# XBEE3_Thing_Plus.net
KiCad netlist of a schematic drawn in EAGLE
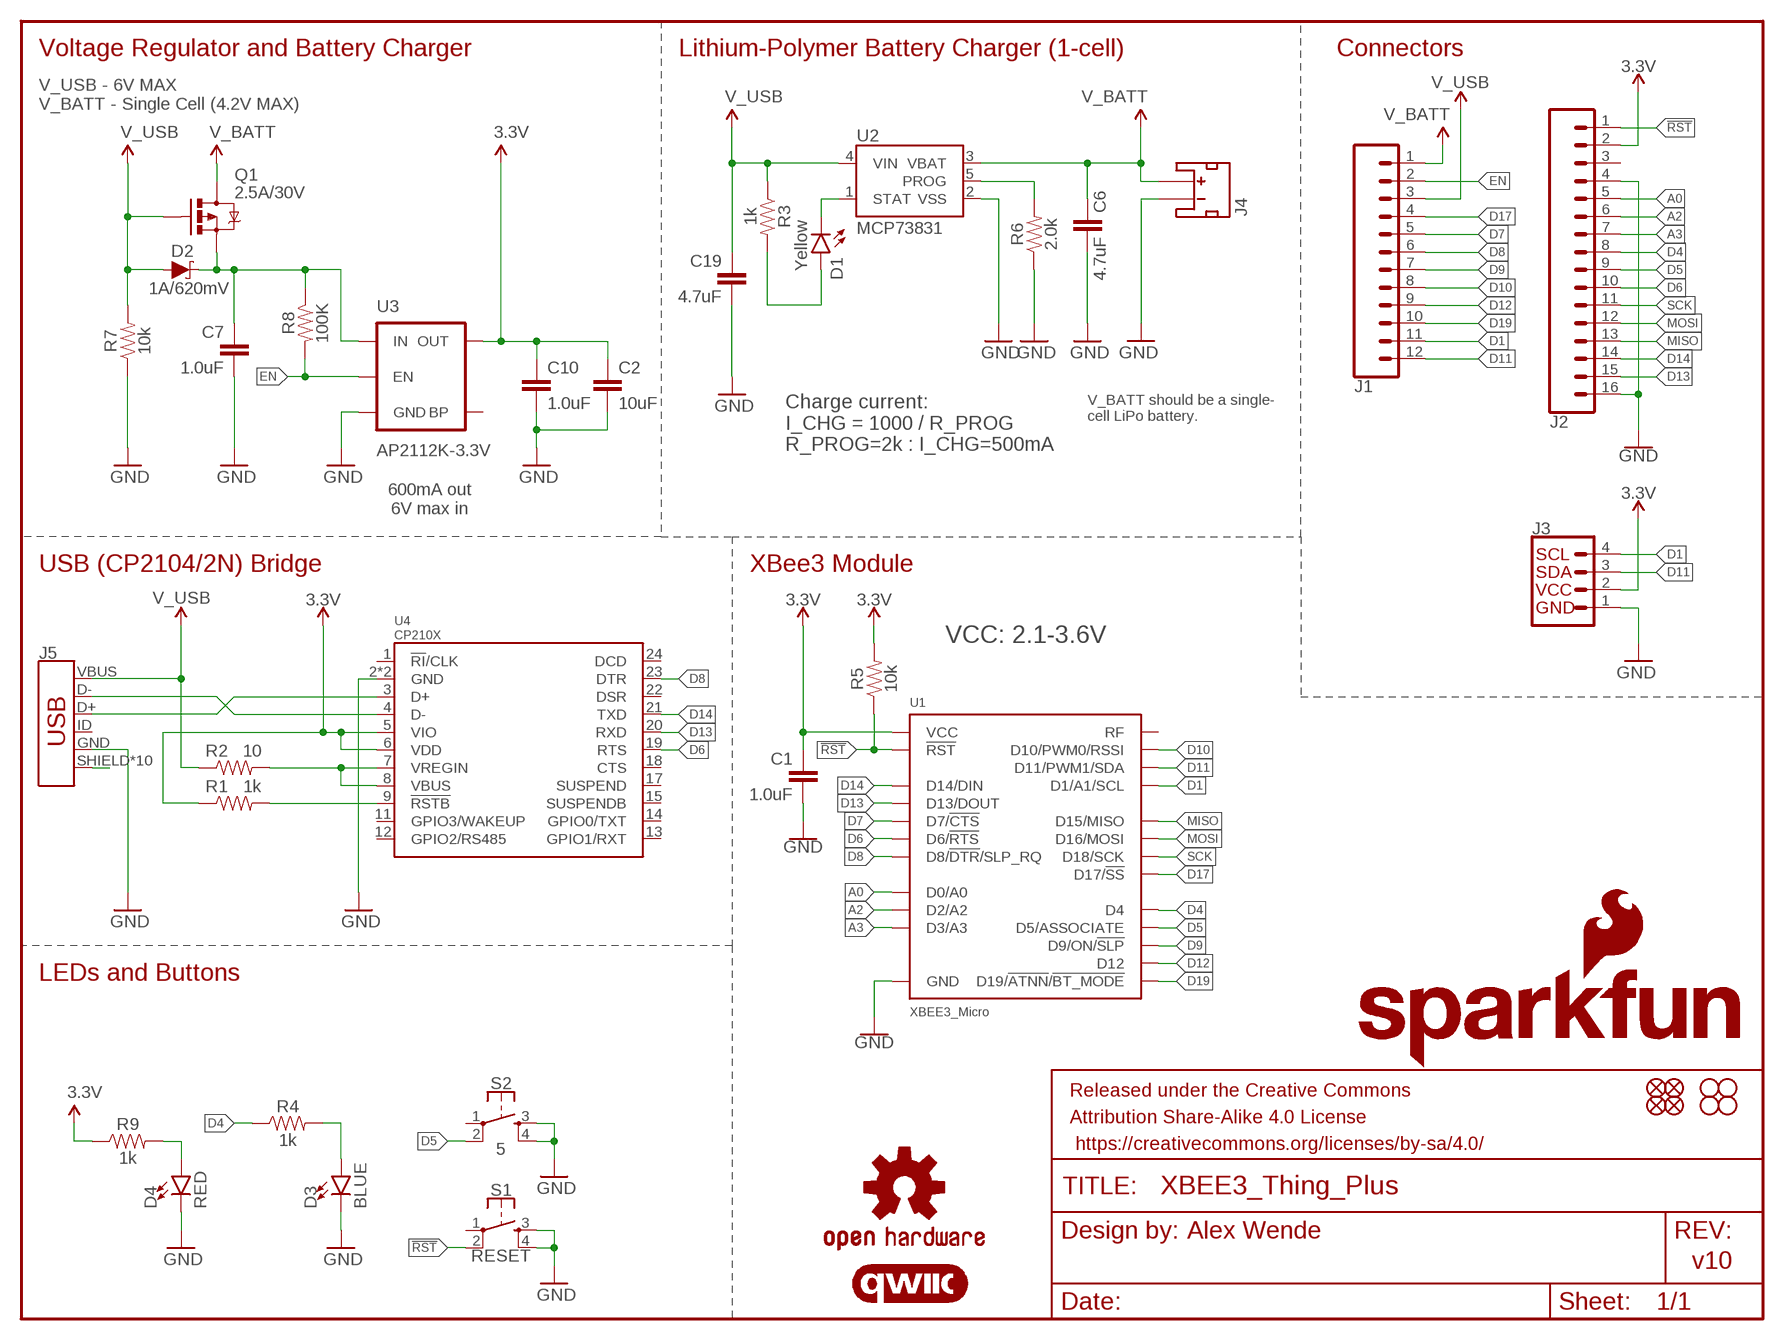
[diagram p0: schematic, sheet 1]

(export (version "E")
  (design (tool "Eeschema 10.0.6"))
  (components
    (comp (ref "C1")
      (value "1.0uF")
      (footprint "eagle-import:0603")
      (libsource (lib "eagle-import") (part "1.0UF-0603-16V-10%"))
    )
    (comp (ref "C2")
      (value "10uF")
      (footprint "eagle-import:0603")
      (libsource (lib "eagle-import") (part "10UF-0603-6.3V-20%"))
    )
    (comp (ref "C6")
      (value "4.7uF")
      (footprint "eagle-import:0603")
      (libsource (lib "eagle-import") (part "4.7UF-0603-6.3V-(10%)"))
    )
    (comp (ref "C7")
      (value "1.0uF")
      (footprint "eagle-import:0603")
      (libsource (lib "eagle-import") (part "1.0UF-0603-16V-10%-X7R"))
    )
    (comp (ref "C10")
      (value "1.0uF")
      (footprint "eagle-import:0402")
      (libsource (lib "eagle-import") (part "1.0UF-0402-16V-10%"))
    )
    (comp (ref "C19")
      (value "4.7uF")
      (footprint "eagle-import:0603")
      (libsource (lib "eagle-import") (part "4.7UF-0603-6.3V-(10%)"))
    )
    (comp (ref "D1")
      (value "Yellow")
      (footprint "eagle-import:LED-0603")
      (libsource (lib "eagle-import") (part "LED-YELLOW0603"))
    )
    (comp (ref "D2")
      (value "1A/620mV")
      (footprint "eagle-import:SOD-323")
      (libsource (lib "eagle-import") (part "DIODE-SCHOTTKY-BAT20J"))
    )
    (comp (ref "D3")
      (value "BLUE")
      (footprint "eagle-import:LED-0603")
      (libsource (lib "eagle-import") (part "LED-BLUE0603"))
    )
    (comp (ref "D4")
      (value "RED")
      (footprint "eagle-import:LED-0603")
      (libsource (lib "eagle-import") (part "LED-RED0603"))
    )
    (comp (ref "FD1")
      (value "FIDUCIALUFIDUCIAL")
      (footprint "eagle-import:FIDUCIAL-MICRO")
      (libsource (lib "eagle-import") (part "FIDUCIALUFIDUCIAL"))
    )
    (comp (ref "FD2")
      (value "FIDUCIALUFIDUCIAL")
      (footprint "eagle-import:FIDUCIAL-MICRO")
      (libsource (lib "eagle-import") (part "FIDUCIALUFIDUCIAL"))
    )
    (comp (ref "FD3")
      (value "FIDUCIALUFIDUCIAL")
      (footprint "eagle-import:FIDUCIAL-MICRO")
      (libsource (lib "eagle-import") (part "FIDUCIALUFIDUCIAL"))
    )
    (comp (ref "FD4")
      (value "FIDUCIALUFIDUCIAL")
      (footprint "eagle-import:FIDUCIAL-MICRO")
      (libsource (lib "eagle-import") (part "FIDUCIALUFIDUCIAL"))
    )
    (comp (ref "FRAME1")
      (value "FRAME-LETTER")
      (footprint "eagle-import:CREATIVE_COMMONS")
      (libsource (lib "eagle-import") (part "FRAME-LETTER"))
    )
    (comp (ref "H1")
      (value "STAND-OFF")
      (footprint "eagle-import:STAND-OFF")
      (libsource (lib "eagle-import") (part "STAND-OFF"))
    )
    (comp (ref "H2")
      (value "STAND-OFF")
      (footprint "eagle-import:STAND-OFF")
      (libsource (lib "eagle-import") (part "STAND-OFF"))
    )
    (comp (ref "H3")
      (value "STAND-OFF")
      (footprint "eagle-import:STAND-OFF")
      (libsource (lib "eagle-import") (part "STAND-OFF"))
    )
    (comp (ref "H4")
      (value "STAND-OFF")
      (footprint "eagle-import:STAND-OFF")
      (libsource (lib "eagle-import") (part "STAND-OFF"))
    )
    (comp (ref "J1")
      (value "CONN_12SM_SQ_NO_SILK")
      (footprint "eagle-import:1X12_SM_SQ_NOSILK")
      (libsource (lib "eagle-import") (part "CONN_12SM_SQ_NO_SILK"))
    )
    (comp (ref "J2")
      (value "CONN_161X16_SM_SQ_NOSILK")
      (footprint "eagle-import:1X16_SM_SQ_NOSILK")
      (libsource (lib "eagle-import") (part "CONN_161X16_SM_SQ_NOSILK"))
    )
    (comp (ref "J3")
      (value "QWIIC_CONNECTORJS-1MM")
      (footprint "eagle-import:JST04_1MM_RA")
      (libsource (lib "eagle-import") (part "QWIIC_CONNECTORJS-1MM"))
    )
    (comp (ref "J4")
      (value "JST_2MM_MALE")
      (footprint "eagle-import:JST-2-SMD")
      (libsource (lib "eagle-import") (part "JST_2MM_MALE"))
    )
    (comp (ref "J5")
      (value "USB_MICRO-B_HALF_PTH_MILL")
      (footprint "eagle-import:USB-MICROB-PTH-MILL")
      (libsource (lib "eagle-import") (part "USB_MICRO-B_HALF_PTH_MILL"))
    )
    (comp (ref "LOGO1")
      (value "SFE_LOGO_NAME_FLAME.1_INCH")
      (footprint "eagle-import:SFE_LOGO_NAME_FLAME_.1")
      (libsource (lib "eagle-import") (part "SFE_LOGO_NAME_FLAME.1_INCH"))
    )
    (comp (ref "LOGO2")
      (value "OSHW-LOGOS")
      (footprint "eagle-import:OSHW-LOGO-S")
      (libsource (lib "eagle-import") (part "OSHW-LOGOS"))
    )
    (comp (ref "Q1")
      (value "2.5A/30V")
      (footprint "eagle-import:SOT23-3@1")
      (libsource (lib "eagle-import") (part "MOSFET-PCHANNELDMG2307L"))
    )
    (comp (ref "R1")
      (value "1k")
      (footprint "eagle-import:0603")
      (libsource (lib "eagle-import") (part "1KOHM-0603-1/10W-1%"))
    )
    (comp (ref "R2")
      (value "10")
      (footprint "eagle-import:0603")
      (libsource (lib "eagle-import") (part "10OHM-0603-1/10W-1%"))
    )
    (comp (ref "R3")
      (value "1k")
      (footprint "eagle-import:0603")
      (libsource (lib "eagle-import") (part "1KOHM-0603-1/10W-1%"))
    )
    (comp (ref "R4")
      (value "1k")
      (footprint "eagle-import:0603")
      (libsource (lib "eagle-import") (part "1KOHM-0603-1/10W-1%"))
    )
    (comp (ref "R5")
      (value "10k")
      (footprint "eagle-import:0603")
      (libsource (lib "eagle-import") (part "10KOHM-0603-1/10W-1%"))
    )
    (comp (ref "R6")
      (value "2.0k")
      (footprint "eagle-import:0603")
      (libsource (lib "eagle-import") (part "2.0KOHM1/10W5%(0603)"))
    )
    (comp (ref "R7")
      (value "10k")
      (footprint "eagle-import:0603")
      (libsource (lib "eagle-import") (part "10KOHM-0603-1/10W-1%"))
    )
    (comp (ref "R8")
      (value "100K")
      (footprint "eagle-import:0402")
      (libsource (lib "eagle-import") (part "100KOHM-0402-1/16W-1%"))
    )
    (comp (ref "R9")
      (value "1k")
      (footprint "eagle-import:0603")
      (libsource (lib "eagle-import") (part "1KOHM-0603-1/10W-1%"))
    )
    (comp (ref "S1")
      (value "RESET")
      (footprint "eagle-import:TACTILE_SWITCH_SMD_4.6X2.8MM")
      (libsource (lib "eagle-import") (part "MOMENTARY-SWITCH-SPST-2-SMD-4.6X2.8MM"))
    )
    (comp (ref "S2")
      (value "5")
      (footprint "eagle-import:TACTILE_SWITCH_SMD_4.6X2.8MM")
      (libsource (lib "eagle-import") (part "MOMENTARY-SWITCH-SPST-2-SMD-4.6X2.8MM"))
    )
    (comp (ref "U$63")
      (value "QWIIC_LOGO_5MM")
      (footprint "eagle-import:QWIIC_5MM")
      (libsource (lib "eagle-import") (part "QWIIC_LOGO_5MM"))
    )
    (comp (ref "U1")
      (value "XBEE3_Micro")
      (footprint "eagle-import:XBEE3")
      (libsource (lib "eagle-import") (part "XBEE3"))
    )
    (comp (ref "U2")
      (value "MCP73831")
      (footprint "eagle-import:SOT23-5")
      (libsource (lib "eagle-import") (part "MCP73831"))
    )
    (comp (ref "U3")
      (value "AP2112K-3.3V")
      (footprint "eagle-import:SOT23-5")
      (libsource (lib "eagle-import") (part "V_REG_LDOSMD"))
    )
    (comp (ref "U4")
      (value "CP210X")
      (footprint "eagle-import:QFN24")
      (libsource (lib "eagle-import") (part "CP2102N"))
    )
  )
  (nets
    (net (code "1") (name "/~{RST}") (class "Default")
      (node (ref "J2") (pin "1") (pinfunction "1_1") (pintype "passive"))
      (node (ref "R5") (pin "1") (pinfunction "1_1") (pintype "passive"))
      (node (ref "S1") (pin "2") (pinfunction "2_2") (pintype "passive"))
      (node (ref "U1") (pin "P$6") (pinfunction "~{RST}_P$6") (pintype "input"))
    )
    (net (code "2") (name "3.3V") (class "Default")
      (node (ref "C1") (pin "1") (pinfunction "1_1") (pintype "passive"))
      (node (ref "C10") (pin "1") (pinfunction "1_1") (pintype "passive"))
      (node (ref "C2") (pin "1") (pinfunction "1_1") (pintype "passive"))
      (node (ref "J2") (pin "2") (pinfunction "2_2") (pintype "passive"))
      (node (ref "J3") (pin "2") (pinfunction "2_2") (pintype "power_in"))
      (node (ref "R1") (pin "1") (pinfunction "1_1") (pintype "passive"))
      (node (ref "R5") (pin "2") (pinfunction "2_2") (pintype "passive"))
      (node (ref "R9") (pin "1") (pinfunction "1_1") (pintype "passive"))
      (node (ref "U1") (pin "P$2") (pinfunction "VCC_P$2") (pintype "bidirectional"))
      (node (ref "U3") (pin "5") (pinfunction "OUT_5") (pintype "passive"))
      (node (ref "U4") (pin "5") (pinfunction "VIO_5") (pintype "bidirectional"))
      (node (ref "U4") (pin "6") (pinfunction "VDD_6") (pintype "bidirectional"))
    )
    (net (code "3") (name "A0") (class "Default")
      (node (ref "J2") (pin "5") (pinfunction "5_5") (pintype "passive"))
      (node (ref "U1") (pin "P$31") (pinfunction "D0/A0_P$31") (pintype "bidirectional"))
    )
    (net (code "4") (name "A2") (class "Default")
      (node (ref "J2") (pin "6") (pinfunction "6_6") (pintype "passive"))
      (node (ref "U1") (pin "P$29") (pinfunction "D2/A2_P$29") (pintype "bidirectional"))
    )
    (net (code "5") (name "A3") (class "Default")
      (node (ref "J2") (pin "7") (pinfunction "7_7") (pintype "passive"))
      (node (ref "U1") (pin "P$28") (pinfunction "D3/A3_P$28") (pintype "bidirectional"))
    )
    (net (code "6") (name "D1") (class "Default")
      (node (ref "J1") (pin "11") (pinfunction "11_11") (pintype "passive"))
      (node (ref "J3") (pin "4") (pinfunction "4_4") (pintype "passive"))
      (node (ref "U1") (pin "P$30") (pinfunction "D1/A1/SCL_P$30") (pintype "bidirectional"))
    )
    (net (code "7") (name "D4") (class "Default")
      (node (ref "J2") (pin "8") (pinfunction "8_8") (pintype "passive"))
      (node (ref "R4") (pin "1") (pinfunction "1_1") (pintype "passive"))
      (node (ref "U1") (pin "P$23") (pinfunction "D4_P$23") (pintype "bidirectional"))
    )
    (net (code "8") (name "D5") (class "Default")
      (node (ref "J2") (pin "9") (pinfunction "9_9") (pintype "passive"))
      (node (ref "S2") (pin "2") (pinfunction "2_2") (pintype "passive"))
      (node (ref "U1") (pin "P$26") (pinfunction "D5/ASSOCIATE_P$26") (pintype "bidirectional"))
    )
    (net (code "9") (name "D6") (class "Default")
      (node (ref "J2") (pin "10") (pinfunction "10_10") (pintype "passive"))
      (node (ref "U1") (pin "P$27") (pinfunction "D6/~{RTS}_P$27") (pintype "bidirectional"))
      (node (ref "U4") (pin "19") (pinfunction "RTS_19") (pintype "bidirectional"))
    )
    (net (code "10") (name "D7") (class "Default")
      (node (ref "J1") (pin "5") (pinfunction "5_5") (pintype "passive"))
      (node (ref "U1") (pin "P$24") (pinfunction "D7/~{CTS}_P$24") (pintype "bidirectional"))
    )
    (net (code "11") (name "D8") (class "Default")
      (node (ref "J1") (pin "6") (pinfunction "6_6") (pintype "passive"))
      (node (ref "U1") (pin "P$9") (pinfunction "D8/~{DTR}/SLP_RQ_P$9") (pintype "bidirectional"))
      (node (ref "U4") (pin "23") (pinfunction "DTR_23") (pintype "bidirectional"))
    )
    (net (code "12") (name "D9") (class "Default")
      (node (ref "J1") (pin "7") (pinfunction "7_7") (pintype "passive"))
      (node (ref "U1") (pin "P$25") (pinfunction "D9/ON/~{SLP}_P$25") (pintype "bidirectional"))
    )
    (net (code "13") (name "D10") (class "Default")
      (node (ref "J1") (pin "8") (pinfunction "8_8") (pintype "passive"))
      (node (ref "U1") (pin "P$7") (pinfunction "D10/PWM0/RSSI_P$7") (pintype "bidirectional"))
    )
    (net (code "14") (name "D11") (class "Default")
      (node (ref "J1") (pin "12") (pinfunction "12_12") (pintype "passive"))
      (node (ref "J3") (pin "3") (pinfunction "3_3") (pintype "passive"))
      (node (ref "U1") (pin "P$8") (pinfunction "D11/PWM1/SDA_P$8") (pintype "bidirectional"))
    )
    (net (code "15") (name "D12") (class "Default")
      (node (ref "J1") (pin "9") (pinfunction "9_9") (pintype "passive"))
      (node (ref "U1") (pin "P$5") (pinfunction "D12_P$5") (pintype "bidirectional"))
    )
    (net (code "16") (name "D13") (class "Default")
      (node (ref "J2") (pin "15") (pinfunction "15_15") (pintype "passive"))
      (node (ref "U1") (pin "P$3") (pinfunction "D13/DOUT_P$3") (pintype "bidirectional"))
      (node (ref "U4") (pin "20") (pinfunction "RXD_20") (pintype "bidirectional"))
    )
    (net (code "17") (name "D14") (class "Default")
      (node (ref "J2") (pin "14") (pinfunction "14_14") (pintype "passive"))
      (node (ref "U1") (pin "P$4") (pinfunction "D14/DIN_P$4") (pintype "bidirectional"))
      (node (ref "U4") (pin "21") (pinfunction "TXD_21") (pintype "bidirectional"))
    )
    (net (code "18") (name "D17") (class "Default")
      (node (ref "J1") (pin "4") (pinfunction "4_4") (pintype "passive"))
      (node (ref "U1") (pin "P$14") (pinfunction "D17/~{SS}_P$14") (pintype "bidirectional"))
    )
    (net (code "19") (name "D19") (class "Default")
      (node (ref "J1") (pin "10") (pinfunction "10_10") (pintype "passive"))
      (node (ref "U1") (pin "P$11") (pinfunction "D19/~{ATNN}/~{BT_MODE}_P$11") (pintype "bidirectional"))
    )
    (net (code "20") (name "EN") (class "Default")
      (node (ref "J1") (pin "2") (pinfunction "2_2") (pintype "passive"))
      (node (ref "R8") (pin "2") (pinfunction "2_2") (pintype "passive"))
      (node (ref "U3") (pin "3") (pinfunction "EN_3") (pintype "input"))
    )
    (net (code "21") (name "GND") (class "Default")
      (node (ref "C1") (pin "2") (pinfunction "2_2") (pintype "passive"))
      (node (ref "C10") (pin "2") (pinfunction "2_2") (pintype "passive"))
      (node (ref "C19") (pin "2") (pinfunction "2_2") (pintype "passive"))
      (node (ref "C2") (pin "2") (pinfunction "2_2") (pintype "passive"))
      (node (ref "C6") (pin "2") (pinfunction "2_2") (pintype "passive"))
      (node (ref "C7") (pin "2") (pinfunction "2_2") (pintype "passive"))
      (node (ref "D3") (pin "C") (pinfunction "C_C") (pintype "passive"))
      (node (ref "D4") (pin "C") (pinfunction "C_C") (pintype "passive"))
      (node (ref "J2") (pin "16") (pinfunction "16_16") (pintype "passive"))
      (node (ref "J2") (pin "4") (pinfunction "4_4") (pintype "passive"))
      (node (ref "J3") (pin "1") (pinfunction "1_1") (pintype "power_in"))
      (node (ref "J4") (pin "1") (pinfunction "-_1") (pintype "bidirectional"))
      (node (ref "J5") (pin "GND") (pinfunction "GND_GND") (pintype "power_in"))
      (node (ref "R6") (pin "1") (pinfunction "1_1") (pintype "passive"))
      (node (ref "R7") (pin "1") (pinfunction "1_1") (pintype "passive"))
      (node (ref "S1") (pin "3") (pinfunction "3_3") (pintype "passive"))
      (node (ref "S1") (pin "4") (pinfunction "4_4") (pintype "passive"))
      (node (ref "S2") (pin "3") (pinfunction "3_3") (pintype "passive"))
      (node (ref "S2") (pin "4") (pinfunction "4_4") (pintype "passive"))
      (node (ref "U1") (pin "P$1") (pinfunction "GND_P$1") (pintype "bidirectional"))
      (node (ref "U1") (pin "P$10") (pinfunction "GND_P$10") (pintype "bidirectional"))
      (node (ref "U1") (pin "P$12") (pinfunction "GND_P$12") (pintype "bidirectional"))
      (node (ref "U1") (pin "P$21") (pinfunction "GND_P$21") (pintype "bidirectional"))
      (node (ref "U1") (pin "P$32") (pinfunction "GND_P$32") (pintype "bidirectional"))
      (node (ref "U1") (pin "P$34") (pinfunction "GND_P$34") (pintype "bidirectional"))
      (node (ref "U2") (pin "2") (pinfunction "VSS_2") (pintype "power_in"))
      (node (ref "U3") (pin "2") (pinfunction "GND_2") (pintype "input"))
      (node (ref "U4") (pin "2") (pinfunction "GND_2") (pintype "bidirectional"))
      (node (ref "U4") (pin "PAD") (pinfunction "GND_PAD") (pintype "bidirectional"))
    )
    (net (code "22") (name "MISO") (class "Default")
      (node (ref "J2") (pin "13") (pinfunction "13_13") (pintype "passive"))
      (node (ref "U1") (pin "P$16") (pinfunction "D15/MISO_P$16") (pintype "bidirectional"))
    )
    (net (code "23") (name "MOSI") (class "Default")
      (node (ref "J2") (pin "12") (pinfunction "12_12") (pintype "passive"))
      (node (ref "U1") (pin "P$15") (pinfunction "D16/MOSI_P$15") (pintype "bidirectional"))
    )
    (net (code "24") (name "Net-(D1-PadA)") (class "Default")
      (node (ref "D1") (pin "A") (pinfunction "A_A") (pintype "passive"))
      (node (ref "R3") (pin "2") (pinfunction "2_2") (pintype "passive"))
    )
    (net (code "25") (name "Net-(D3-PadA)") (class "Default")
      (node (ref "D3") (pin "A") (pinfunction "A_A") (pintype "passive"))
      (node (ref "R4") (pin "2") (pinfunction "2_2") (pintype "passive"))
    )
    (net (code "26") (name "Net-(D4-PadA)") (class "Default")
      (node (ref "D4") (pin "A") (pinfunction "A_A") (pintype "passive"))
      (node (ref "R9") (pin "2") (pinfunction "2_2") (pintype "passive"))
    )
    (net (code "27") (name "Net-(J5-PadSHIELD)") (class "Default")
      (node (ref "J5") (pin "SHIELD") (pinfunction "SHIELD_SHIELD") (pintype "bidirectional"))
      (node (ref "J5") (pin "SHIELD10") (pinfunction "SHIELD_SHIELD10") (pintype "bidirectional"))
      (node (ref "J5") (pin "SHIELD2") (pinfunction "SHIELD_SHIELD2") (pintype "bidirectional"))
      (node (ref "J5") (pin "SHIELD3") (pinfunction "SHIELD_SHIELD3") (pintype "bidirectional"))
      (node (ref "J5") (pin "SHIELD4") (pinfunction "SHIELD_SHIELD4") (pintype "bidirectional"))
      (node (ref "J5") (pin "SHIELD5") (pinfunction "SHIELD_SHIELD5") (pintype "bidirectional"))
      (node (ref "J5") (pin "SHIELD6") (pinfunction "SHIELD_SHIELD6") (pintype "bidirectional"))
      (node (ref "J5") (pin "SHIELD7") (pinfunction "SHIELD_SHIELD7") (pintype "bidirectional"))
      (node (ref "J5") (pin "SHIELD8") (pinfunction "SHIELD_SHIELD8") (pintype "bidirectional"))
      (node (ref "J5") (pin "SHIELD9") (pinfunction "SHIELD_SHIELD9") (pintype "bidirectional"))
    )
    (net (code "28") (name "Net-(Q1-S)") (class "Default")
      (node (ref "C7") (pin "1") (pinfunction "1_1") (pintype "passive"))
      (node (ref "D2") (pin "C") (pinfunction "C_C") (pintype "passive"))
      (node (ref "Q1") (pin "2") (pinfunction "S_2") (pintype "passive"))
      (node (ref "R8") (pin "1") (pinfunction "1_1") (pintype "passive"))
      (node (ref "U3") (pin "1") (pinfunction "IN_1") (pintype "input"))
    )
    (net (code "29") (name "Net-(U2-PROG)") (class "Default")
      (node (ref "R6") (pin "2") (pinfunction "2_2") (pintype "passive"))
      (node (ref "U2") (pin "5") (pinfunction "PROG_5") (pintype "input"))
    )
    (net (code "30") (name "Net-(U2-STAT)") (class "Default")
      (node (ref "D1") (pin "C") (pinfunction "C_C") (pintype "passive"))
      (node (ref "U2") (pin "1") (pinfunction "STAT_1") (pintype "output"))
    )
    (net (code "31") (name "Net-(U4-D+)") (class "Default")
      (node (ref "J5") (pin "D+") (pinfunction "D+_D+") (pintype "bidirectional"))
      (node (ref "U4") (pin "3") (pinfunction "D+_3") (pintype "bidirectional"))
    )
    (net (code "32") (name "Net-(U4-D-)") (class "Default")
      (node (ref "J5") (pin "D-") (pinfunction "D-_D-") (pintype "bidirectional"))
      (node (ref "U4") (pin "4") (pinfunction "D-_4") (pintype "bidirectional"))
    )
    (net (code "33") (name "Net-(U4-VBUS)") (class "Default")
      (node (ref "R2") (pin "2") (pinfunction "2_2") (pintype "passive"))
      (node (ref "U4") (pin "7") (pinfunction "VREGIN_7") (pintype "bidirectional"))
      (node (ref "U4") (pin "8") (pinfunction "VBUS_8") (pintype "bidirectional"))
    )
    (net (code "34") (name "Net-(U4-~{RSTB})") (class "Default")
      (node (ref "R1") (pin "2") (pinfunction "2_2") (pintype "passive"))
      (node (ref "U4") (pin "9") (pinfunction "~{RSTB}_9") (pintype "bidirectional"))
    )
    (net (code "35") (name "SCK") (class "Default")
      (node (ref "J2") (pin "11") (pinfunction "11_11") (pintype "passive"))
      (node (ref "U1") (pin "P$13") (pinfunction "D18/SCK_P$13") (pintype "bidirectional"))
    )
    (net (code "36") (name "V_BATT") (class "Default")
      (node (ref "C6") (pin "1") (pinfunction "1_1") (pintype "passive"))
      (node (ref "J1") (pin "1") (pinfunction "1_1") (pintype "passive"))
      (node (ref "J4") (pin "2") (pinfunction "+_2") (pintype "bidirectional"))
      (node (ref "Q1") (pin "3") (pinfunction "D_3") (pintype "passive"))
      (node (ref "U2") (pin "3") (pinfunction "VBAT_3") (pintype "power_in"))
    )
    (net (code "37") (name "V_USB") (class "Default")
      (node (ref "C19") (pin "1") (pinfunction "1_1") (pintype "passive"))
      (node (ref "D2") (pin "A") (pinfunction "A_A") (pintype "passive"))
      (node (ref "J1") (pin "3") (pinfunction "3_3") (pintype "passive"))
      (node (ref "J5") (pin "VBUS") (pinfunction "VBUS_VBUS") (pintype "power_in"))
      (node (ref "Q1") (pin "1") (pinfunction "G_1") (pintype "passive"))
      (node (ref "R2") (pin "1") (pinfunction "1_1") (pintype "passive"))
      (node (ref "R3") (pin "1") (pinfunction "1_1") (pintype "passive"))
      (node (ref "R7") (pin "2") (pinfunction "2_2") (pintype "passive"))
      (node (ref "U2") (pin "4") (pinfunction "VIN_4") (pintype "power_in"))
    )
    (net (code "38") (name "unconnected-(J2-Pad3)") (class "Default")
      (node (ref "J2") (pin "3") (pinfunction "3_3") (pintype "passive"))
    )
    (net (code "39") (name "unconnected-(J4-PAD1-PadNC1)") (class "Default")
      (node (ref "J4") (pin "NC1") (pinfunction "PAD1_NC1") (pintype "bidirectional"))
    )
    (net (code "40") (name "unconnected-(J4-PAD2-PadNC2)") (class "Default")
      (node (ref "J4") (pin "NC2") (pinfunction "PAD2_NC2") (pintype "bidirectional"))
    )
    (net (code "41") (name "unconnected-(J5-PadID)") (class "Default")
      (node (ref "J5") (pin "ID") (pinfunction "ID_ID") (pintype "bidirectional"))
    )
    (net (code "42") (name "unconnected-(S1-Pad1)") (class "Default")
      (node (ref "S1") (pin "1") (pinfunction "1_1") (pintype "passive"))
    )
    (net (code "43") (name "unconnected-(S2-Pad1)") (class "Default")
      (node (ref "S2") (pin "1") (pinfunction "1_1") (pintype "passive"))
    )
    (net (code "44") (name "unconnected-(U1-RF-PadP$33)") (class "Default")
      (node (ref "U1") (pin "P$33") (pinfunction "RF_P$33") (pintype "bidirectional"))
    )
    (net (code "45") (name "unconnected-(U3-BP-Pad4)") (class "Default")
      (node (ref "U3") (pin "4") (pinfunction "BP_4") (pintype "input"))
    )
    (net (code "46") (name "unconnected-(U4-CTS-Pad18)") (class "Default")
      (node (ref "U4") (pin "18") (pinfunction "CTS_18") (pintype "bidirectional"))
    )
    (net (code "47") (name "unconnected-(U4-DCD-Pad24)") (class "Default")
      (node (ref "U4") (pin "24") (pinfunction "DCD_24") (pintype "bidirectional"))
    )
    (net (code "48") (name "unconnected-(U4-DSR-Pad22)") (class "Default")
      (node (ref "U4") (pin "22") (pinfunction "DSR_22") (pintype "bidirectional"))
    )
    (net (code "49") (name "unconnected-(U4-GPIO0{slash}TXT-Pad14)") (class "Default")
      (node (ref "U4") (pin "14") (pinfunction "GPIO0/TXT_14") (pintype "bidirectional"))
    )
    (net (code "50") (name "unconnected-(U4-GPIO1{slash}RXT-Pad13)") (class "Default")
      (node (ref "U4") (pin "13") (pinfunction "GPIO1/RXT_13") (pintype "bidirectional"))
    )
    (net (code "51") (name "unconnected-(U4-GPIO2{slash}RS485-Pad12)") (class "Default")
      (node (ref "U4") (pin "12") (pinfunction "GPIO2/RS485_12") (pintype "bidirectional"))
    )
    (net (code "52") (name "unconnected-(U4-GPIO3{slash}WAKEUP-Pad11)") (class "Default")
      (node (ref "U4") (pin "11") (pinfunction "GPIO3/WAKEUP_11") (pintype "bidirectional"))
    )
    (net (code "53") (name "unconnected-(U4-SUSPEND-Pad17)") (class "Default")
      (node (ref "U4") (pin "17") (pinfunction "SUSPEND_17") (pintype "bidirectional"))
    )
    (net (code "54") (name "unconnected-(U4-SUSPENDB-Pad15)") (class "Default")
      (node (ref "U4") (pin "15") (pinfunction "SUSPENDB_15") (pintype "bidirectional"))
    )
    (net (code "55") (name "unconnected-(U4-~{RI}{slash}CLK-Pad1)") (class "Default")
      (node (ref "U4") (pin "1") (pinfunction "~{RI}/CLK_1") (pintype "bidirectional"))
    )
  )
)
